# ADC.net
KiCad netlist of a schematic drawn in Altium Designer
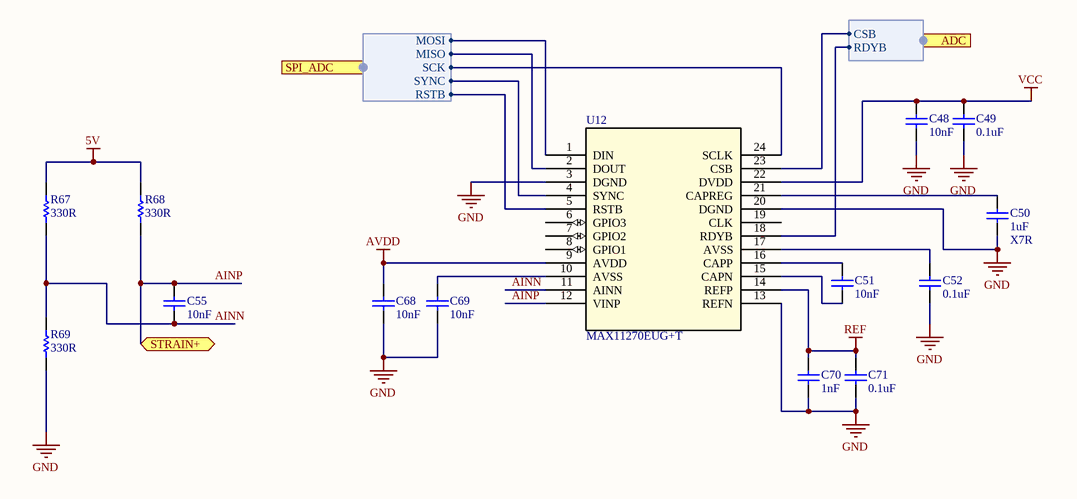
[diagram p0: ADC.SchDoc]

(export (version "E")
  (design (tool "Eeschema 10.0.6"))
  (components
    (comp (ref "C48")
      (value "10nF")
      (footprint "C0603[1608X92]")
      (description "10nF 6.3V 10% 0603 (1608 Metric)")
      (fields (field (name "PARTNUMBER") "GRM188R70J103KA01D") (field (name "MANUFACTURER") "Murata"))
      (libsource (lib "Capacitors") (part "CAP_10nF_6.3V_0603_10%"))
    )
    (comp (ref "C49")
      (value "0.1uF")
      (footprint "C0603[1608X92]")
      (description "0.1uF 6.3V 10% 0603 (1608 Metric)")
      (fields (field (name "PARTNUMBER") "GRM188R70J104KA01D") (field (name "MANUFACTURER") "Murata"))
      (libsource (lib "Capacitors") (part "CAP_0.1uF_6.3V_0603_10%"))
    )
    (comp (ref "C50")
      (value "1uF")
      (footprint "C0603[1608X92]")
      (description "1uF 16V 10% 0603 X7R (1608 Metric)")
      (fields
        (field (name "PARTNUMBER") "GCJ188R71E105KA01D")
        (field (name "MANUFACTURER") "Murata")
        (field (name "TEMPERATURECOEFFICIENT") "X7R")
      )
      (libsource (lib "Capacitors") (part "CAP_1uF_16V_0603_10%_X7R"))
    )
    (comp (ref "C51")
      (value "10nF")
      (footprint "C0603[1608X92]")
      (description "10nF 6.3V 10% 0603 (1608 Metric)")
      (fields (field (name "PARTNUMBER") "GRM188R70J103KA01D") (field (name "MANUFACTURER") "Murata"))
      (libsource (lib "Capacitors") (part "CAP_10nF_6.3V_0603_10%"))
    )
    (comp (ref "C52")
      (value "0.1uF")
      (footprint "C0603[1608X92]")
      (description "0.1uF 6.3V 10% 0603 (1608 Metric)")
      (fields (field (name "PARTNUMBER") "GRM188R70J104KA01D") (field (name "MANUFACTURER") "Murata"))
      (libsource (lib "Capacitors") (part "CAP_0.1uF_6.3V_0603_10%"))
    )
    (comp (ref "C55")
      (value "10nF")
      (footprint "C0603[1608X92]")
      (description "10nF 6.3V 10% 0603 (1608 Metric)")
      (fields (field (name "PARTNUMBER") "GRM188R70J103KA01D") (field (name "MANUFACTURER") "Murata"))
      (libsource (lib "Capacitors") (part "CAP_10nF_6.3V_0603_10%"))
    )
    (comp (ref "C68")
      (value "10nF")
      (footprint "C0603[1608X92]")
      (description "10nF 6.3V 10% 0603 (1608 Metric)")
      (fields (field (name "PARTNUMBER") "GRM188R70J103KA01D") (field (name "MANUFACTURER") "Murata"))
      (libsource (lib "Capacitors") (part "CAP_10nF_6.3V_0603_10%"))
    )
    (comp (ref "C69")
      (value "10nF")
      (footprint "C0603[1608X92]")
      (description "10nF 6.3V 10% 0603 (1608 Metric)")
      (fields (field (name "PARTNUMBER") "GRM188R70J103KA01D") (field (name "MANUFACTURER") "Murata"))
      (libsource (lib "Capacitors") (part "CAP_10nF_6.3V_0603_10%"))
    )
    (comp (ref "C70")
      (value "1nF")
      (footprint "C0603[1608X92]")
      (description "1nF 6.3V 5% 0603 (1608 Metric)")
      (fields (field (name "PARTNUMBER") "06036C102KAT4A") (field (name "MANUFACTURER") "AVX Corporation"))
      (libsource (lib "Capacitors") (part "CAP_1nF_6.3V_0603_5%"))
    )
    (comp (ref "C71")
      (value "0.1uF")
      (footprint "C0603[1608X92]")
      (description "0.1uF 6.3V 10% 0603 (1608 Metric)")
      (fields (field (name "PARTNUMBER") "GRM188R70J104KA01D") (field (name "MANUFACTURER") "Murata"))
      (libsource (lib "Capacitors") (part "CAP_0.1uF_6.3V_0603_10%"))
    )
    (comp (ref "R67")
      (value "330R")
      (footprint "R0603[1608]")
      (description "330R 0.2W 1% 0603 (1005 Metric)")
      (fields (field (name "MANUFACTURER") "Panasonic") (field (name "PARTNUMBER") "ERJ-PB3B3300V"))
      (libsource (lib "Resistors") (part "RES_330R_0603_0.1%"))
    )
    (comp (ref "R68")
      (value "330R")
      (footprint "R0603[1608]")
      (description "330R 0.2W 1% 0603 (1005 Metric)")
      (fields (field (name "MANUFACTURER") "Panasonic") (field (name "PARTNUMBER") "ERJ-PB3B3300V"))
      (libsource (lib "Resistors") (part "RES_330R_0603_0.1%"))
    )
    (comp (ref "R69")
      (value "330R")
      (footprint "R0603[1608]")
      (description "330R 0.2W 1% 0603 (1005 Metric)")
      (fields (field (name "MANUFACTURER") "Panasonic") (field (name "PARTNUMBER") "ERJ-PB3B3300V"))
      (libsource (lib "Resistors") (part "RES_330R_0603_0.1%"))
    )
    (comp (ref "U12")
      (value "MAX11270EUG+T")
      (footprint "21-0066J_24")
      (description "Imported")
      (fields (field (name "PARTNUMBER") "MAX111270EUG+T") (field (name "MANUFACTURER") "Maxim"))
      (libsource (lib "General_Component") (part "MAX11270EUG+T"))
    )
  )
  (nets
    (net (code "3") (name "/AINN") (class "Default")
      (node (ref "C55") (pin "1") (pinfunction "1_1") (pintype "passive"))
      (node (ref "R67") (pin "1") (pinfunction "1_1") (pintype "passive"))
      (node (ref "R69") (pin "2") (pinfunction "2_2") (pintype "passive"))
      (node (ref "U12") (pin "11") (pinfunction "AINN_11") (pintype "passive"))
    )
    (net (code "4") (name "/AINP") (class "Default")
      (node (ref "C55") (pin "2") (pinfunction "2_2") (pintype "passive"))
      (node (ref "R68") (pin "1") (pinfunction "1_1") (pintype "passive"))
      (node (ref "U12") (pin "12") (pinfunction "VINP_12") (pintype "passive"))
    )
    (net (code "5") (name "/CSB") (class "Default")
      (node (ref "U12") (pin "23") (pinfunction "CSB_23") (pintype "passive"))
    )
    (net (code "6") (name "/MISO") (class "Default")
      (node (ref "U12") (pin "2") (pinfunction "DOUT_2") (pintype "passive"))
    )
    (net (code "7") (name "/MOSI") (class "Default")
      (node (ref "U12") (pin "1") (pinfunction "DIN_1") (pintype "passive"))
    )
    (net (code "8") (name "/RDYB") (class "Default")
      (node (ref "U12") (pin "18") (pinfunction "RDYB_18") (pintype "passive"))
    )
    (net (code "9") (name "/RSTB") (class "Default")
      (node (ref "U12") (pin "5") (pinfunction "RSTB_5") (pintype "passive"))
    )
    (net (code "10") (name "/SCK") (class "Default")
      (node (ref "U12") (pin "24") (pinfunction "SCLK_24") (pintype "passive"))
    )
    (net (code "11") (name "/SYNC") (class "Default")
      (node (ref "U12") (pin "4") (pinfunction "SYNC_4") (pintype "passive"))
    )
    (net (code "14") (name "5V") (class "Default")
      (node (ref "R67") (pin "2") (pinfunction "2_2") (pintype "passive"))
      (node (ref "R68") (pin "2") (pinfunction "2_2") (pintype "passive"))
    )
    (net (code "15") (name "AVDD") (class "Default")
      (node (ref "C68") (pin "2") (pinfunction "2_2") (pintype "passive"))
      (node (ref "U12") (pin "9") (pinfunction "AVDD_9") (pintype "power_in"))
    )
    (net (code "16") (name "GND") (class "Default")
      (node (ref "C48") (pin "1") (pinfunction "1_1") (pintype "passive"))
      (node (ref "C49") (pin "1") (pinfunction "1_1") (pintype "passive"))
      (node (ref "C50") (pin "1") (pinfunction "1_1") (pintype "passive"))
      (node (ref "C52") (pin "1") (pinfunction "1_1") (pintype "passive"))
      (node (ref "C68") (pin "1") (pinfunction "1_1") (pintype "passive"))
      (node (ref "C69") (pin "1") (pinfunction "1_1") (pintype "passive"))
      (node (ref "C70") (pin "1") (pinfunction "1_1") (pintype "passive"))
      (node (ref "C71") (pin "1") (pinfunction "1_1") (pintype "passive"))
      (node (ref "R69") (pin "1") (pinfunction "1_1") (pintype "passive"))
      (node (ref "U12") (pin "13") (pinfunction "REFN_13") (pintype "passive"))
      (node (ref "U12") (pin "20") (pinfunction "DGND_20") (pintype "power_in"))
      (node (ref "U12") (pin "3") (pinfunction "DGND_3") (pintype "power_in"))
    )
    (net (code "17") (name "Net-(C52-Pad2)") (class "Default")
      (node (ref "C52") (pin "2") (pinfunction "2_2") (pintype "passive"))
      (node (ref "U12") (pin "17") (pinfunction "AVSS_17") (pintype "power_in"))
    )
    (net (code "18") (name "Net-(C69-Pad2)") (class "Default")
      (node (ref "C69") (pin "2") (pinfunction "2_2") (pintype "passive"))
      (node (ref "U12") (pin "10") (pinfunction "AVSS_10") (pintype "power_in"))
    )
    (net (code "19") (name "Net-(U12-CAPN)") (class "Default")
      (node (ref "C51") (pin "1") (pinfunction "1_1") (pintype "passive"))
      (node (ref "U12") (pin "15") (pinfunction "CAPN_15") (pintype "passive"))
    )
    (net (code "20") (name "Net-(U12-CAPP)") (class "Default")
      (node (ref "C51") (pin "2") (pinfunction "2_2") (pintype "passive"))
      (node (ref "U12") (pin "16") (pinfunction "CAPP_16") (pintype "passive"))
    )
    (net (code "21") (name "Net-(U12-CAPREG)") (class "Default")
      (node (ref "C50") (pin "2") (pinfunction "2_2") (pintype "passive"))
      (node (ref "U12") (pin "21") (pinfunction "CAPREG_21") (pintype "power_in"))
    )
    (net (code "22") (name "REF") (class "Default")
      (node (ref "C70") (pin "2") (pinfunction "2_2") (pintype "passive"))
      (node (ref "C71") (pin "2") (pinfunction "2_2") (pintype "passive"))
      (node (ref "U12") (pin "14") (pinfunction "REFP_14") (pintype "passive"))
    )
    (net (code "23") (name "VCC") (class "Default")
      (node (ref "C48") (pin "2") (pinfunction "2_2") (pintype "passive"))
      (node (ref "C49") (pin "2") (pinfunction "2_2") (pintype "passive"))
      (node (ref "U12") (pin "22") (pinfunction "DVDD_22") (pintype "power_in"))
    )
    (net (code "24") (name "unconnected-(U12-CLK-Pad19)") (class "Default")
      (node (ref "U12") (pin "19") (pinfunction "CLK_19") (pintype "passive"))
    )
    (net (code "25") (name "unconnected-(U12-GPIO1-Pad8)") (class "Default")
      (node (ref "U12") (pin "8") (pinfunction "GPIO1_8") (pintype "bidirectional"))
    )
    (net (code "26") (name "unconnected-(U12-GPIO2-Pad7)") (class "Default")
      (node (ref "U12") (pin "7") (pinfunction "GPIO2_7") (pintype "bidirectional"))
    )
    (net (code "27") (name "unconnected-(U12-GPIO3-Pad6)") (class "Default")
      (node (ref "U12") (pin "6") (pinfunction "GPIO3_6") (pintype "bidirectional"))
    )
  )
)
